# Sensorboard_Schematic.net
KiCad netlist of a schematic drawn in Altium Designer
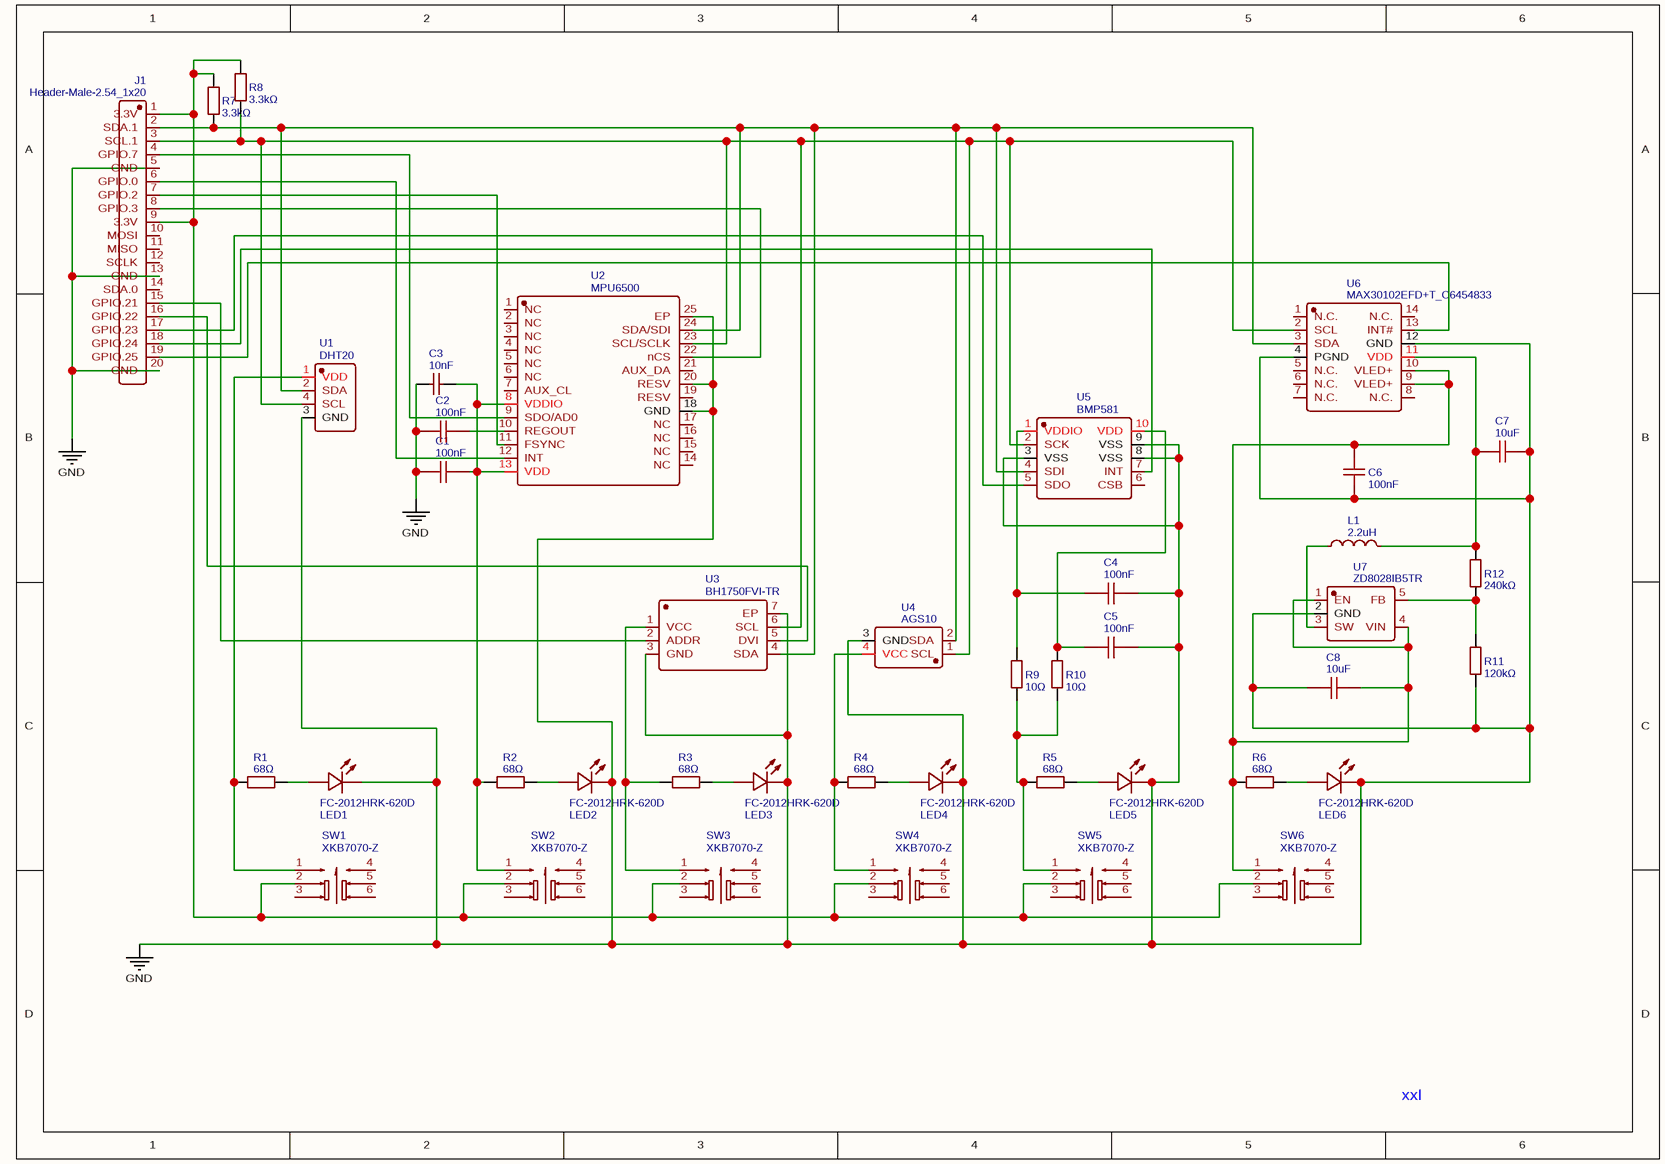
[diagram p0: Sensorboard_Schematic.schdoc]

(export (version "E")
  (design (tool "Eeschema 10.0.6"))
  (components
    (comp (ref "C1")
      (value "100nF")
      (fields
        (field (name "MANUFACTURER") "YAGEO(国巨)")
        (field (name "MANUFACTURER PART") "CC0603KRX7R9BB104")
      )
      (libsource (lib "altium-import") (part "root_0_100nF_"))
    )
    (comp (ref "C2")
      (value "100nF")
      (fields
        (field (name "MANUFACTURER") "YAGEO(国巨)")
        (field (name "MANUFACTURER PART") "CC0603KRX7R9BB104")
      )
      (libsource (lib "altium-import") (part "root_0_100nF_"))
    )
    (comp (ref "C3")
      (value "10nF")
      (fields
        (field (name "MANUFACTURER") "YAGEO(国巨)")
        (field (name "MANUFACTURER PART") "CC0603KRX7R9BB103")
      )
      (libsource (lib "altium-import") (part "root_0_10nF_"))
    )
    (comp (ref "C4")
      (value "100nF")
      (fields
        (field (name "MANUFACTURER") "YAGEO(国巨)")
        (field (name "MANUFACTURER PART") "CC0603KRX7R9BB104")
      )
      (libsource (lib "altium-import") (part "root_0_100nF_"))
    )
    (comp (ref "C5")
      (value "100nF")
      (fields
        (field (name "MANUFACTURER") "YAGEO(国巨)")
        (field (name "MANUFACTURER PART") "CC0603KRX7R9BB104")
      )
      (libsource (lib "altium-import") (part "root_0_100nF_"))
    )
    (comp (ref "C6")
      (value "100nF")
      (fields
        (field (name "MANUFACTURER") "YAGEO(国巨)")
        (field (name "MANUFACTURER PART") "CC0603KRX7R9BB104")
      )
      (libsource (lib "altium-import") (part "root_3_100nF_"))
    )
    (comp (ref "C7")
      (value "10uF")
      (fields
        (field (name "MANUFACTURER PART") "CL21A106KAYNNNE")
        (field (name "MANUFACTURER") "SAMSUNG(三星)")
      )
      (libsource (lib "altium-import") (part "root_0_10uF_"))
    )
    (comp (ref "C8")
      (value "10uF")
      (fields
        (field (name "MANUFACTURER PART") "CL21A106KAYNNNE")
        (field (name "MANUFACTURER") "SAMSUNG(三星)")
      )
      (libsource (lib "altium-import") (part "root_0_10uF_"))
    )
    (comp (ref "J1")
      (value "Header-Male-2.54_1x20")
      (fields (field (name "MANUFACTURER") "BOOMELE(博穆精密)") (field (name "MANUFACTURER PART") "2.54-1*20P直针"))
      (libsource (lib "altium-import") (part "root_0_Header-Male-2.54_1x20_"))
    )
    (comp (ref "L1")
      (value "2.2uH")
      (fields (field (name "MANUFACTURER PART") "CMI201209U2R2KT") (field (name "MANUFACTURER") "FH(风华)"))
      (libsource (lib "altium-import") (part "root_0_2.2uH_"))
    )
    (comp (ref "LED1")
      (value "FC-2012HRK-620D")
      (fields (field (name "MANUFACTURER") "国星光电") (field (name "MANUFACTURER PART") "NCD0805R1"))
      (libsource (lib "altium-import") (part "root_2_FC-2012HRK-620D_"))
    )
    (comp (ref "LED2")
      (value "FC-2012HRK-620D")
      (fields (field (name "MANUFACTURER") "国星光电") (field (name "MANUFACTURER PART") "NCD0805R1"))
      (libsource (lib "altium-import") (part "root_2_FC-2012HRK-620D_"))
    )
    (comp (ref "LED3")
      (value "FC-2012HRK-620D")
      (fields (field (name "MANUFACTURER") "国星光电") (field (name "MANUFACTURER PART") "NCD0805R1"))
      (libsource (lib "altium-import") (part "root_2_FC-2012HRK-620D_"))
    )
    (comp (ref "LED4")
      (value "FC-2012HRK-620D")
      (fields (field (name "MANUFACTURER") "国星光电") (field (name "MANUFACTURER PART") "NCD0805R1"))
      (libsource (lib "altium-import") (part "root_2_FC-2012HRK-620D_"))
    )
    (comp (ref "LED5")
      (value "FC-2012HRK-620D")
      (fields (field (name "MANUFACTURER") "国星光电") (field (name "MANUFACTURER PART") "NCD0805R1"))
      (libsource (lib "altium-import") (part "root_2_FC-2012HRK-620D_"))
    )
    (comp (ref "LED6")
      (value "FC-2012HRK-620D")
      (fields (field (name "MANUFACTURER") "国星光电") (field (name "MANUFACTURER PART") "NCD0805R1"))
      (libsource (lib "altium-import") (part "root_2_FC-2012HRK-620D_"))
    )
    (comp (ref "R1")
      (value "68Ω")
      (fields
        (field (name "MANUFACTURER") "UNI-ROYAL(厚声)")
        (field (name "MANUFACTURER PART") "0805W8F680JT5E")
      )
      (libsource (lib "altium-import") (part "root_0_68Ω_"))
    )
    (comp (ref "R2")
      (value "68Ω")
      (fields
        (field (name "MANUFACTURER") "UNI-ROYAL(厚声)")
        (field (name "MANUFACTURER PART") "0805W8F680JT5E")
      )
      (libsource (lib "altium-import") (part "root_0_68Ω_"))
    )
    (comp (ref "R3")
      (value "68Ω")
      (fields
        (field (name "MANUFACTURER") "UNI-ROYAL(厚声)")
        (field (name "MANUFACTURER PART") "0805W8F680JT5E")
      )
      (libsource (lib "altium-import") (part "root_0_68Ω_"))
    )
    (comp (ref "R4")
      (value "68Ω")
      (fields
        (field (name "MANUFACTURER") "UNI-ROYAL(厚声)")
        (field (name "MANUFACTURER PART") "0805W8F680JT5E")
      )
      (libsource (lib "altium-import") (part "root_0_68Ω_"))
    )
    (comp (ref "R5")
      (value "68Ω")
      (fields
        (field (name "MANUFACTURER") "UNI-ROYAL(厚声)")
        (field (name "MANUFACTURER PART") "0805W8F680JT5E")
      )
      (libsource (lib "altium-import") (part "root_0_68Ω_"))
    )
    (comp (ref "R6")
      (value "68Ω")
      (fields
        (field (name "MANUFACTURER") "UNI-ROYAL(厚声)")
        (field (name "MANUFACTURER PART") "0805W8F680JT5E")
      )
      (libsource (lib "altium-import") (part "root_0_68Ω_"))
    )
    (comp (ref "R7")
      (value "3.3kΩ")
      (fields
        (field (name "MANUFACTURER") "UNI-ROYAL(厚声)")
        (field (name "MANUFACTURER PART") "0603WAF3301T5E")
      )
      (libsource (lib "altium-import") (part "root_1_3.3kΩ_"))
    )
    (comp (ref "R8")
      (value "3.3kΩ")
      (fields
        (field (name "MANUFACTURER") "UNI-ROYAL(厚声)")
        (field (name "MANUFACTURER PART") "0603WAF3301T5E")
      )
      (libsource (lib "altium-import") (part "root_3_3.3kΩ_"))
    )
    (comp (ref "R9")
      (value "10Ω")
      (fields
        (field (name "MANUFACTURER") "UNI-ROYAL(厚声)")
        (field (name "MANUFACTURER PART") "0603WAF100JT5E")
      )
      (libsource (lib "altium-import") (part "root_1_10Ω_"))
    )
    (comp (ref "R10")
      (value "10Ω")
      (fields
        (field (name "MANUFACTURER") "UNI-ROYAL(厚声)")
        (field (name "MANUFACTURER PART") "0603WAF100JT5E")
      )
      (libsource (lib "altium-import") (part "root_3_10Ω_"))
    )
    (comp (ref "R11")
      (value "120kΩ")
      (fields
        (field (name "MANUFACTURER") "UNI-ROYAL(厚声)")
        (field (name "MANUFACTURER PART") "0603WAF1203T5E")
      )
      (libsource (lib "altium-import") (part "root_1_120kΩ_"))
    )
    (comp (ref "R12")
      (value "240kΩ")
      (fields
        (field (name "MANUFACTURER") "UNI-ROYAL(厚声)")
        (field (name "MANUFACTURER PART") "0603WAF2403T5E")
      )
      (libsource (lib "altium-import") (part "root_1_240kΩ_"))
    )
    (comp (ref "SW1")
      (value "XKB7070-Z")
      (fields (field (name "MANUFACTURER") "XKB Connectivity(中国星坤)") (field (name "CONTRIBUTOR") "LCSC"))
      (libsource (lib "altium-import") (part "root_0_XKB7070-Z_"))
    )
    (comp (ref "SW2")
      (value "XKB7070-Z")
      (fields (field (name "MANUFACTURER") "XKB Connectivity(中国星坤)") (field (name "CONTRIBUTOR") "LCSC"))
      (libsource (lib "altium-import") (part "root_0_XKB7070-Z_"))
    )
    (comp (ref "SW3")
      (value "XKB7070-Z")
      (fields (field (name "MANUFACTURER") "XKB Connectivity(中国星坤)") (field (name "CONTRIBUTOR") "LCSC"))
      (libsource (lib "altium-import") (part "root_0_XKB7070-Z_"))
    )
    (comp (ref "SW4")
      (value "XKB7070-Z")
      (fields (field (name "MANUFACTURER") "XKB Connectivity(中国星坤)") (field (name "CONTRIBUTOR") "LCSC"))
      (libsource (lib "altium-import") (part "root_0_XKB7070-Z_"))
    )
    (comp (ref "SW5")
      (value "XKB7070-Z")
      (fields (field (name "MANUFACTURER") "XKB Connectivity(中国星坤)") (field (name "CONTRIBUTOR") "LCSC"))
      (libsource (lib "altium-import") (part "root_0_XKB7070-Z_"))
    )
    (comp (ref "SW6")
      (value "XKB7070-Z")
      (fields (field (name "MANUFACTURER") "XKB Connectivity(中国星坤)") (field (name "CONTRIBUTOR") "LCSC"))
      (libsource (lib "altium-import") (part "root_0_XKB7070-Z_"))
    )
    (comp (ref "U1")
      (value "DHT20")
      (fields (field (name "MANUFACTURER") "广州奥松") (field (name "CONTRIBUTOR") "lcsc"))
      (libsource (lib "altium-import") (part "root_0_DHT20_"))
    )
    (comp (ref "U2")
      (value "MPU6500")
      (fields
        (field (name "MANUFACTURER") "TDK InvenSense(应美盛)")
        (field (name "MANUFACTURER PART") "MPU-6500")
      )
      (libsource (lib "altium-import") (part "root_0_MPU6500_"))
    )
    (comp (ref "U3")
      (value "BH1750FVI-TR")
      (fields (field (name "MANUFACTURER") "ROHM(罗姆)"))
      (libsource (lib "altium-import") (part "root_0_BH1750FVI-TR_"))
    )
    (comp (ref "U4")
      (value "AGS10")
      (fields (field (name "MANUFACTURER") "广州奥松") (field (name "CONTRIBUTOR") "lcsc"))
      (libsource (lib "altium-import") (part "root_2_AGS10_"))
    )
    (comp (ref "U5")
      (value "BMP581")
      (fields (field (name "MANUFACTURER") "Bosch(博世)") (field (name "CONTRIBUTOR") "lcsc"))
      (libsource (lib "altium-import") (part "root_0_BMP581_"))
    )
    (comp (ref "U6")
      (value "MAX30102EFD+T_C6454833")
      (fields
        (field (name "MANUFACTURER") "ADI(亚德诺)/MAXIM(美信)")
        (field (name "MANUFACTURER PART") "MAX30102EFD+T")
      )
      (libsource (lib "altium-import") (part "root_0_MAX30102EFD+T_C6454833_"))
    )
    (comp (ref "U7")
      (value "ZD8028IB5TR")
      (fields (field (name "MANUFACTURER") "Zetta(澜智)") (field (name "CONTRIBUTOR") "lcsc"))
      (libsource (lib "altium-import") (part "root_0_ZD8028IB5TR_"))
    )
  )
  (nets
    (net (code "1") (name "GND") (class "Default")
      (node (ref "C1") (pin "1") (pinfunction "1_1") (pintype "passive"))
      (node (ref "C2") (pin "1") (pinfunction "1_1") (pintype "passive"))
      (node (ref "C3") (pin "1") (pinfunction "1_1") (pintype "passive"))
      (node (ref "C4") (pin "2") (pinfunction "2_2") (pintype "passive"))
      (node (ref "C5") (pin "2") (pinfunction "2_2") (pintype "passive"))
      (node (ref "C6") (pin "2") (pinfunction "2_2") (pintype "passive"))
      (node (ref "C7") (pin "2") (pinfunction "2_2") (pintype "passive"))
      (node (ref "C8") (pin "1") (pinfunction "1_1") (pintype "passive"))
      (node (ref "J1") (pin "13") (pinfunction "GND_13") (pintype "passive"))
      (node (ref "J1") (pin "20") (pinfunction "GND_20") (pintype "passive"))
      (node (ref "J1") (pin "5") (pinfunction "GND_5") (pintype "passive"))
      (node (ref "LED1") (pin "2") (pinfunction "-_2") (pintype "passive"))
      (node (ref "LED2") (pin "2") (pinfunction "-_2") (pintype "passive"))
      (node (ref "LED3") (pin "2") (pinfunction "-_2") (pintype "passive"))
      (node (ref "LED4") (pin "2") (pinfunction "-_2") (pintype "passive"))
      (node (ref "LED5") (pin "2") (pinfunction "-_2") (pintype "passive"))
      (node (ref "LED6") (pin "2") (pinfunction "-_2") (pintype "passive"))
      (node (ref "R11") (pin "1") (pinfunction "1_1") (pintype "passive"))
      (node (ref "U1") (pin "3") (pinfunction "GND_3") (pintype "passive"))
      (node (ref "U2") (pin "18") (pinfunction "GND_18") (pintype "passive"))
      (node (ref "U2") (pin "20") (pinfunction "RESV_20") (pintype "passive"))
      (node (ref "U2") (pin "25") (pinfunction "EP_25") (pintype "passive"))
      (node (ref "U3") (pin "3") (pinfunction "GND_3") (pintype "passive"))
      (node (ref "U3") (pin "7") (pinfunction "EP_7") (pintype "passive"))
      (node (ref "U4") (pin "3") (pinfunction "GND_3") (pintype "passive"))
      (node (ref "U5") (pin "3") (pinfunction "VSS_3") (pintype "passive"))
      (node (ref "U5") (pin "8") (pinfunction "VSS_8") (pintype "passive"))
      (node (ref "U5") (pin "9") (pinfunction "VSS_9") (pintype "passive"))
      (node (ref "U6") (pin "12") (pinfunction "GND_12") (pintype "passive"))
      (node (ref "U6") (pin "4") (pinfunction "PGND_4") (pintype "passive"))
      (node (ref "U7") (pin "2") (pinfunction "GND_2") (pintype "passive"))
    )
    (net (code "2") (name "Net-(J1-3.3V-Pad1)") (class "Default")
      (node (ref "J1") (pin "1") (pinfunction "3.3V_1") (pintype "passive"))
      (node (ref "J1") (pin "9") (pinfunction "3.3V_9") (pintype "passive"))
      (node (ref "R7") (pin "2") (pinfunction "2_2") (pintype "passive"))
      (node (ref "R8") (pin "1") (pinfunction "1_1") (pintype "passive"))
      (node (ref "SW1") (pin "2") (pinfunction "2_2") (pintype "passive"))
      (node (ref "SW2") (pin "2") (pinfunction "2_2") (pintype "passive"))
      (node (ref "SW3") (pin "2") (pinfunction "2_2") (pintype "passive"))
      (node (ref "SW4") (pin "2") (pinfunction "2_2") (pintype "passive"))
      (node (ref "SW5") (pin "2") (pinfunction "2_2") (pintype "passive"))
      (node (ref "SW6") (pin "2") (pinfunction "2_2") (pintype "passive"))
    )
    (net (code "3") (name "Net-(J1-GPIO.0)") (class "Default")
      (node (ref "J1") (pin "6") (pinfunction "GPIO.0_6") (pintype "passive"))
      (node (ref "U2") (pin "12") (pinfunction "INT_12") (pintype "passive"))
    )
    (net (code "4") (name "Net-(J1-GPIO.2)") (class "Default")
      (node (ref "J1") (pin "7") (pinfunction "GPIO.2_7") (pintype "passive"))
      (node (ref "U2") (pin "11") (pinfunction "FSYNC_11") (pintype "passive"))
    )
    (net (code "5") (name "Net-(J1-GPIO.3)") (class "Default")
      (node (ref "J1") (pin "8") (pinfunction "GPIO.3_8") (pintype "passive"))
      (node (ref "U2") (pin "22") (pinfunction "nCS_22") (pintype "passive"))
    )
    (net (code "6") (name "Net-(J1-GPIO.7)") (class "Default")
      (node (ref "J1") (pin "4") (pinfunction "GPIO.7_4") (pintype "passive"))
      (node (ref "U2") (pin "9") (pinfunction "SDO/AD0_9") (pintype "passive"))
    )
    (net (code "7") (name "Net-(J1-GPIO.21)") (class "Default")
      (node (ref "J1") (pin "15") (pinfunction "GPIO.21_15") (pintype "passive"))
      (node (ref "U3") (pin "2") (pinfunction "ADDR_2") (pintype "passive"))
    )
    (net (code "8") (name "Net-(J1-GPIO.22)") (class "Default")
      (node (ref "J1") (pin "16") (pinfunction "GPIO.22_16") (pintype "passive"))
      (node (ref "U3") (pin "5") (pinfunction "DVI_5") (pintype "passive"))
    )
    (net (code "9") (name "Net-(J1-GPIO.23)") (class "Default")
      (node (ref "J1") (pin "17") (pinfunction "GPIO.23_17") (pintype "passive"))
      (node (ref "U5") (pin "5") (pinfunction "SDO_5") (pintype "passive"))
    )
    (net (code "10") (name "Net-(J1-GPIO.24)") (class "Default")
      (node (ref "J1") (pin "18") (pinfunction "GPIO.24_18") (pintype "passive"))
      (node (ref "U5") (pin "7") (pinfunction "INT_7") (pintype "passive"))
    )
    (net (code "11") (name "Net-(J1-GPIO.25)") (class "Default")
      (node (ref "J1") (pin "19") (pinfunction "GPIO.25_19") (pintype "passive"))
      (node (ref "U6") (pin "13") (pinfunction "INT#_13") (pintype "passive"))
    )
    (net (code "12") (name "Net-(J1-SCL.1)") (class "Default")
      (node (ref "J1") (pin "3") (pinfunction "SCL.1_3") (pintype "passive"))
      (node (ref "R8") (pin "2") (pinfunction "2_2") (pintype "passive"))
      (node (ref "U1") (pin "4") (pinfunction "SCL_4") (pintype "passive"))
      (node (ref "U2") (pin "23") (pinfunction "SCL/SCLK_23") (pintype "passive"))
      (node (ref "U3") (pin "6") (pinfunction "SCL_6") (pintype "passive"))
      (node (ref "U4") (pin "1") (pinfunction "SCL_1") (pintype "passive"))
      (node (ref "U5") (pin "2") (pinfunction "SCK_2") (pintype "passive"))
      (node (ref "U6") (pin "2") (pinfunction "SCL_2") (pintype "passive"))
    )
    (net (code "13") (name "Net-(J1-SDA.1)") (class "Default")
      (node (ref "J1") (pin "2") (pinfunction "SDA.1_2") (pintype "passive"))
      (node (ref "R7") (pin "1") (pinfunction "1_1") (pintype "passive"))
      (node (ref "U1") (pin "2") (pinfunction "SDA_2") (pintype "passive"))
      (node (ref "U2") (pin "24") (pinfunction "SDA/SDI_24") (pintype "passive"))
      (node (ref "U3") (pin "4") (pinfunction "SDA_4") (pintype "passive"))
      (node (ref "U4") (pin "2") (pinfunction "SDA_2") (pintype "passive"))
      (node (ref "U5") (pin "4") (pinfunction "SDI_4") (pintype "passive"))
      (node (ref "U6") (pin "3") (pinfunction "SDA_3") (pintype "passive"))
    )
    (net (code "14") (name "Net-(LED1-+)") (class "Default")
      (node (ref "LED1") (pin "1") (pinfunction "+_1") (pintype "passive"))
      (node (ref "R1") (pin "2") (pinfunction "2_2") (pintype "passive"))
    )
    (net (code "15") (name "Net-(LED2-+)") (class "Default")
      (node (ref "LED2") (pin "1") (pinfunction "+_1") (pintype "passive"))
      (node (ref "R2") (pin "2") (pinfunction "2_2") (pintype "passive"))
    )
    (net (code "16") (name "Net-(LED3-+)") (class "Default")
      (node (ref "LED3") (pin "1") (pinfunction "+_1") (pintype "passive"))
      (node (ref "R3") (pin "2") (pinfunction "2_2") (pintype "passive"))
    )
    (net (code "17") (name "Net-(LED4-+)") (class "Default")
      (node (ref "LED4") (pin "1") (pinfunction "+_1") (pintype "passive"))
      (node (ref "R4") (pin "2") (pinfunction "2_2") (pintype "passive"))
    )
    (net (code "18") (name "Net-(LED5-+)") (class "Default")
      (node (ref "LED5") (pin "1") (pinfunction "+_1") (pintype "passive"))
      (node (ref "R5") (pin "2") (pinfunction "2_2") (pintype "passive"))
    )
    (net (code "19") (name "Net-(LED6-+)") (class "Default")
      (node (ref "LED6") (pin "1") (pinfunction "+_1") (pintype "passive"))
      (node (ref "R6") (pin "2") (pinfunction "2_2") (pintype "passive"))
    )
    (net (code "20") (name "Net-(R10-Pad2)") (class "Default")
      (node (ref "R10") (pin "2") (pinfunction "2_2") (pintype "passive"))
      (node (ref "R5") (pin "1") (pinfunction "1_1") (pintype "passive"))
      (node (ref "R9") (pin "1") (pinfunction "1_1") (pintype "passive"))
      (node (ref "SW5") (pin "1") (pinfunction "1_1") (pintype "passive"))
    )
    (net (code "21") (name "Net-(U1-VDD)") (class "Default")
      (node (ref "R1") (pin "1") (pinfunction "1_1") (pintype "passive"))
      (node (ref "SW1") (pin "1") (pinfunction "1_1") (pintype "passive"))
      (node (ref "U1") (pin "1") (pinfunction "VDD_1") (pintype "passive"))
    )
    (net (code "22") (name "Net-(U2-REGOUT)") (class "Default")
      (node (ref "C2") (pin "2") (pinfunction "2_2") (pintype "passive"))
      (node (ref "U2") (pin "10") (pinfunction "REGOUT_10") (pintype "passive"))
    )
    (net (code "23") (name "Net-(U2-VDD)") (class "Default")
      (node (ref "C1") (pin "2") (pinfunction "2_2") (pintype "passive"))
      (node (ref "C3") (pin "2") (pinfunction "2_2") (pintype "passive"))
      (node (ref "R2") (pin "1") (pinfunction "1_1") (pintype "passive"))
      (node (ref "SW2") (pin "1") (pinfunction "1_1") (pintype "passive"))
      (node (ref "U2") (pin "13") (pinfunction "VDD_13") (pintype "passive"))
      (node (ref "U2") (pin "8") (pinfunction "VDDIO_8") (pintype "passive"))
    )
    (net (code "24") (name "Net-(U3-VCC)") (class "Default")
      (node (ref "R3") (pin "1") (pinfunction "1_1") (pintype "passive"))
      (node (ref "SW3") (pin "1") (pinfunction "1_1") (pintype "passive"))
      (node (ref "U3") (pin "1") (pinfunction "VCC_1") (pintype "passive"))
    )
    (net (code "25") (name "Net-(U4-VCC)") (class "Default")
      (node (ref "R4") (pin "1") (pinfunction "1_1") (pintype "passive"))
      (node (ref "SW4") (pin "1") (pinfunction "1_1") (pintype "passive"))
      (node (ref "U4") (pin "4") (pinfunction "VCC_4") (pintype "passive"))
    )
    (net (code "26") (name "Net-(U5-VDD)") (class "Default")
      (node (ref "C5") (pin "1") (pinfunction "1_1") (pintype "passive"))
      (node (ref "R10") (pin "1") (pinfunction "1_1") (pintype "passive"))
      (node (ref "U5") (pin "10") (pinfunction "VDD_10") (pintype "passive"))
    )
    (net (code "27") (name "Net-(U5-VDDIO)") (class "Default")
      (node (ref "C4") (pin "1") (pinfunction "1_1") (pintype "passive"))
      (node (ref "R9") (pin "2") (pinfunction "2_2") (pintype "passive"))
      (node (ref "U5") (pin "1") (pinfunction "VDDIO_1") (pintype "passive"))
    )
    (net (code "28") (name "Net-(U6-VDD)") (class "Default")
      (node (ref "C7") (pin "1") (pinfunction "1_1") (pintype "passive"))
      (node (ref "L1") (pin "2") (pinfunction "2_2") (pintype "passive"))
      (node (ref "R12") (pin "2") (pinfunction "2_2") (pintype "passive"))
      (node (ref "U6") (pin "11") (pinfunction "VDD_11") (pintype "passive"))
    )
    (net (code "29") (name "Net-(U7-EN)") (class "Default")
      (node (ref "C6") (pin "1") (pinfunction "1_1") (pintype "passive"))
      (node (ref "C8") (pin "2") (pinfunction "2_2") (pintype "passive"))
      (node (ref "R6") (pin "1") (pinfunction "1_1") (pintype "passive"))
      (node (ref "SW6") (pin "1") (pinfunction "1_1") (pintype "passive"))
      (node (ref "U6") (pin "10") (pinfunction "VLED+_10") (pintype "passive"))
      (node (ref "U6") (pin "9") (pinfunction "VLED+_9") (pintype "passive"))
      (node (ref "U7") (pin "1") (pinfunction "EN_1") (pintype "passive"))
      (node (ref "U7") (pin "4") (pinfunction "VIN_4") (pintype "passive"))
    )
    (net (code "30") (name "Net-(U7-FB)") (class "Default")
      (node (ref "R11") (pin "2") (pinfunction "2_2") (pintype "passive"))
      (node (ref "R12") (pin "1") (pinfunction "1_1") (pintype "passive"))
      (node (ref "U7") (pin "5") (pinfunction "FB_5") (pintype "passive"))
    )
    (net (code "31") (name "Net-(U7-SW)") (class "Default")
      (node (ref "L1") (pin "1") (pinfunction "1_1") (pintype "passive"))
      (node (ref "U7") (pin "3") (pinfunction "SW_3") (pintype "passive"))
    )
    (net (code "32") (name "unconnected-(J1-MISO-Pad11)") (class "Default")
      (node (ref "J1") (pin "11") (pinfunction "MISO_11") (pintype "passive"))
    )
    (net (code "33") (name "unconnected-(J1-MOSI-Pad10)") (class "Default")
      (node (ref "J1") (pin "10") (pinfunction "MOSI_10") (pintype "passive"))
    )
    (net (code "34") (name "unconnected-(J1-SCLK-Pad12)") (class "Default")
      (node (ref "J1") (pin "12") (pinfunction "SCLK_12") (pintype "passive"))
    )
    (net (code "35") (name "unconnected-(J1-SDA.0-Pad14)") (class "Default")
      (node (ref "J1") (pin "14") (pinfunction "SDA.0_14") (pintype "passive"))
    )
    (net (code "36") (name "unconnected-(SW1-Pad3)") (class "Default")
      (node (ref "SW1") (pin "3") (pinfunction "3_3") (pintype "passive"))
    )
    (net (code "37") (name "unconnected-(SW1-Pad4)") (class "Default")
      (node (ref "SW1") (pin "4") (pinfunction "4_4") (pintype "passive"))
    )
    (net (code "38") (name "unconnected-(SW1-Pad5)") (class "Default")
      (node (ref "SW1") (pin "5") (pinfunction "5_5") (pintype "passive"))
    )
    (net (code "39") (name "unconnected-(SW1-Pad6)") (class "Default")
      (node (ref "SW1") (pin "6") (pinfunction "6_6") (pintype "passive"))
    )
    (net (code "40") (name "unconnected-(SW2-Pad3)") (class "Default")
      (node (ref "SW2") (pin "3") (pinfunction "3_3") (pintype "passive"))
    )
    (net (code "41") (name "unconnected-(SW2-Pad4)") (class "Default")
      (node (ref "SW2") (pin "4") (pinfunction "4_4") (pintype "passive"))
    )
    (net (code "42") (name "unconnected-(SW2-Pad5)") (class "Default")
      (node (ref "SW2") (pin "5") (pinfunction "5_5") (pintype "passive"))
    )
    (net (code "43") (name "unconnected-(SW2-Pad6)") (class "Default")
      (node (ref "SW2") (pin "6") (pinfunction "6_6") (pintype "passive"))
    )
    (net (code "44") (name "unconnected-(SW3-Pad3)") (class "Default")
      (node (ref "SW3") (pin "3") (pinfunction "3_3") (pintype "passive"))
    )
    (net (code "45") (name "unconnected-(SW3-Pad4)") (class "Default")
      (node (ref "SW3") (pin "4") (pinfunction "4_4") (pintype "passive"))
    )
    (net (code "46") (name "unconnected-(SW3-Pad5)") (class "Default")
      (node (ref "SW3") (pin "5") (pinfunction "5_5") (pintype "passive"))
    )
    (net (code "47") (name "unconnected-(SW3-Pad6)") (class "Default")
      (node (ref "SW3") (pin "6") (pinfunction "6_6") (pintype "passive"))
    )
    (net (code "48") (name "unconnected-(SW4-Pad3)") (class "Default")
      (node (ref "SW4") (pin "3") (pinfunction "3_3") (pintype "passive"))
    )
    (net (code "49") (name "unconnected-(SW4-Pad4)") (class "Default")
      (node (ref "SW4") (pin "4") (pinfunction "4_4") (pintype "passive"))
    )
    (net (code "50") (name "unconnected-(SW4-Pad5)") (class "Default")
      (node (ref "SW4") (pin "5") (pinfunction "5_5") (pintype "passive"))
    )
    (net (code "51") (name "unconnected-(SW4-Pad6)") (class "Default")
      (node (ref "SW4") (pin "6") (pinfunction "6_6") (pintype "passive"))
    )
    (net (code "52") (name "unconnected-(SW5-Pad3)") (class "Default")
      (node (ref "SW5") (pin "3") (pinfunction "3_3") (pintype "passive"))
    )
    (net (code "53") (name "unconnected-(SW5-Pad4)") (class "Default")
      (node (ref "SW5") (pin "4") (pinfunction "4_4") (pintype "passive"))
    )
    (net (code "54") (name "unconnected-(SW5-Pad5)") (class "Default")
      (node (ref "SW5") (pin "5") (pinfunction "5_5") (pintype "passive"))
    )
    (net (code "55") (name "unconnected-(SW5-Pad6)") (class "Default")
      (node (ref "SW5") (pin "6") (pinfunction "6_6") (pintype "passive"))
    )
    (net (code "56") (name "unconnected-(SW6-Pad3)") (class "Default")
      (node (ref "SW6") (pin "3") (pinfunction "3_3") (pintype "passive"))
    )
    (net (code "57") (name "unconnected-(SW6-Pad4)") (class "Default")
      (node (ref "SW6") (pin "4") (pinfunction "4_4") (pintype "passive"))
    )
    (net (code "58") (name "unconnected-(SW6-Pad5)") (class "Default")
      (node (ref "SW6") (pin "5") (pinfunction "5_5") (pintype "passive"))
    )
    (net (code "59") (name "unconnected-(SW6-Pad6)") (class "Default")
      (node (ref "SW6") (pin "6") (pinfunction "6_6") (pintype "passive"))
    )
    (net (code "60") (name "unconnected-(U2-AUX_CL-Pad7)") (class "Default")
      (node (ref "U2") (pin "7") (pinfunction "AUX_CL_7") (pintype "passive"))
    )
    (net (code "61") (name "unconnected-(U2-AUX_DA-Pad21)") (class "Default")
      (node (ref "U2") (pin "21") (pinfunction "AUX_DA_21") (pintype "passive"))
    )
    (net (code "62") (name "unconnected-(U2-NC-Pad1)") (class "Default")
      (node (ref "U2") (pin "1") (pinfunction "NC_1") (pintype "passive"))
    )
    (net (code "63") (name "unconnected-(U2-NC-Pad2)") (class "Default")
      (node (ref "U2") (pin "2") (pinfunction "NC_2") (pintype "passive"))
    )
    (net (code "64") (name "unconnected-(U2-NC-Pad3)") (class "Default")
      (node (ref "U2") (pin "3") (pinfunction "NC_3") (pintype "passive"))
    )
    (net (code "65") (name "unconnected-(U2-NC-Pad4)") (class "Default")
      (node (ref "U2") (pin "4") (pinfunction "NC_4") (pintype "passive"))
    )
    (net (code "66") (name "unconnected-(U2-NC-Pad5)") (class "Default")
      (node (ref "U2") (pin "5") (pinfunction "NC_5") (pintype "passive"))
    )
    (net (code "67") (name "unconnected-(U2-NC-Pad6)") (class "Default")
      (node (ref "U2") (pin "6") (pinfunction "NC_6") (pintype "passive"))
    )
    (net (code "68") (name "unconnected-(U2-NC-Pad14)") (class "Default")
      (node (ref "U2") (pin "14") (pinfunction "NC_14") (pintype "passive"))
    )
    (net (code "69") (name "unconnected-(U2-NC-Pad15)") (class "Default")
      (node (ref "U2") (pin "15") (pinfunction "NC_15") (pintype "passive"))
    )
    (net (code "70") (name "unconnected-(U2-NC-Pad16)") (class "Default")
      (node (ref "U2") (pin "16") (pinfunction "NC_16") (pintype "passive"))
    )
    (net (code "71") (name "unconnected-(U2-NC-Pad17)") (class "Default")
      (node (ref "U2") (pin "17") (pinfunction "NC_17") (pintype "passive"))
    )
    (net (code "72") (name "unconnected-(U2-RESV-Pad19)") (class "Default")
      (node (ref "U2") (pin "19") (pinfunction "RESV_19") (pintype "passive"))
    )
    (net (code "73") (name "unconnected-(U5-CSB-Pad6)") (class "Default")
      (node (ref "U5") (pin "6") (pinfunction "CSB_6") (pintype "passive"))
    )
    (net (code "74") (name "unconnected-(U6-N.C.-Pad1)") (class "Default")
      (node (ref "U6") (pin "1") (pinfunction "N.C._1") (pintype "passive"))
    )
    (net (code "75") (name "unconnected-(U6-N.C.-Pad5)") (class "Default")
      (node (ref "U6") (pin "5") (pinfunction "N.C._5") (pintype "passive"))
    )
    (net (code "76") (name "unconnected-(U6-N.C.-Pad6)") (class "Default")
      (node (ref "U6") (pin "6") (pinfunction "N.C._6") (pintype "passive"))
    )
    (net (code "77") (name "unconnected-(U6-N.C.-Pad7)") (class "Default")
      (node (ref "U6") (pin "7") (pinfunction "N.C._7") (pintype "passive"))
    )
    (net (code "78") (name "unconnected-(U6-N.C.-Pad8)") (class "Default")
      (node (ref "U6") (pin "8") (pinfunction "N.C._8") (pintype "passive"))
    )
    (net (code "79") (name "unconnected-(U6-N.C.-Pad14)") (class "Default")
      (node (ref "U6") (pin "14") (pinfunction "N.C._14") (pintype "passive"))
    )
  )
)
